# Sheet.net
KiCad netlist of a schematic drawn in Altium Designer
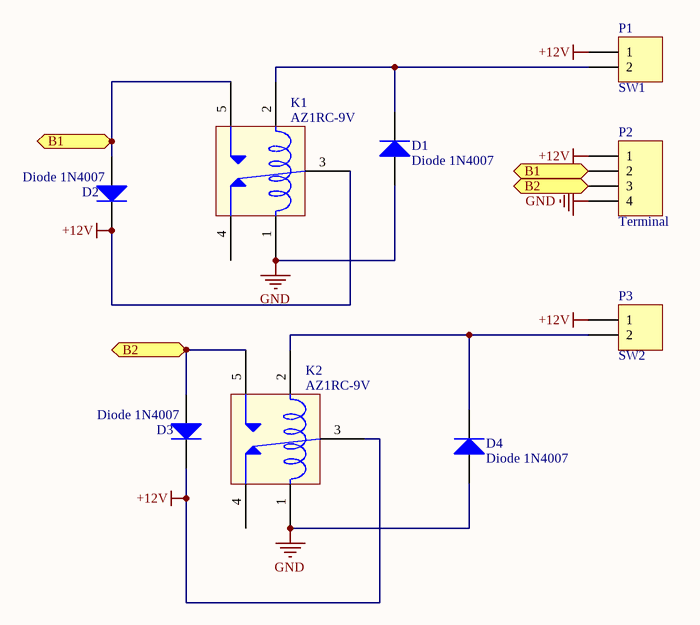
[diagram p0: Sheet.SchDoc]

(export (version "E")
  (design (tool "Eeschema 10.0.6"))
  (components
    (comp (ref "D1")
      (value "Diode 1N4007")
      (footprint "DO-41")
      (description "1 Amp General Purpose Rectifier")
      (fields (field (name "PUBLISHER") "Altium Limited"))
      (libsource (lib "Miscellaneous Devices (1)") (part "Diode 1N4007"))
    )
    (comp (ref "D2")
      (value "Diode 1N4007")
      (footprint "DO-41")
      (description "1 Amp General Purpose Rectifier")
      (fields (field (name "PUBLISHER") "Altium Limited"))
      (libsource (lib "Miscellaneous Devices (1)") (part "Diode 1N4007"))
    )
    (comp (ref "D3")
      (value "Diode 1N4007")
      (footprint "DO-41")
      (description "1 Amp General Purpose Rectifier")
      (fields (field (name "PUBLISHER") "Altium Limited"))
      (libsource (lib "Miscellaneous Devices (1)") (part "Diode 1N4007"))
    )
    (comp (ref "D4")
      (value "Diode 1N4007")
      (footprint "DO-41")
      (description "1 Amp General Purpose Rectifier")
      (fields (field (name "PUBLISHER") "Altium Limited"))
      (libsource (lib "Miscellaneous Devices (1)") (part "Diode 1N4007"))
    )
    (comp (ref "K1")
      (value "AZ1RC-9V")
      (footprint "Relay-A")
      (description "Miniature Relay, 10 A, 9 Vdc, 250 Vac")
      (libsource (lib "GPDSE") (part "AZ1RC-9V"))
    )
    (comp (ref "K2")
      (value "AZ1RC-9V")
      (footprint "Relay-A")
      (description "Miniature Relay, 10 A, 9 Vdc, 250 Vac")
      (libsource (lib "GPDSE") (part "AZ1RC-9V"))
    )
    (comp (ref "P1")
      (value "SW1")
      (footprint "KRE_2")
      (description "Terminal Block 1x2")
      (libsource (lib "GPDSE") (part "KRE_2"))
    )
    (comp (ref "P2")
      (value "Terminal")
      (footprint "KRE_4")
      (description "Terminal Block 1x4")
      (libsource (lib "GPDSE") (part "KRE_4"))
    )
    (comp (ref "P3")
      (value "SW2")
      (footprint "KRE_2")
      (description "Terminal Block 1x2")
      (libsource (lib "GPDSE") (part "KRE_2"))
    )
  )
  (nets
    (net (code "1") (name "+12V") (class "Default")
      (node (ref "D2") (pin "2") (pinfunction "K_2") (pintype "passive"))
      (node (ref "D3") (pin "2") (pinfunction "K_2") (pintype "passive"))
      (node (ref "K1") (pin "3") (pinfunction "3_3") (pintype "passive"))
      (node (ref "K2") (pin "3") (pinfunction "3_3") (pintype "passive"))
      (node (ref "P1") (pin "1") (pinfunction "1_1") (pintype "passive"))
      (node (ref "P2") (pin "1") (pinfunction "1_1") (pintype "passive"))
      (node (ref "P3") (pin "1") (pinfunction "1_1") (pintype "passive"))
    )
    (net (code "2") (name "/B1") (class "Default")
      (node (ref "D2") (pin "1") (pinfunction "A_1") (pintype "passive"))
      (node (ref "K1") (pin "5") (pinfunction "5_5") (pintype "passive"))
      (node (ref "P2") (pin "2") (pinfunction "2_2") (pintype "passive"))
    )
    (net (code "3") (name "/B2") (class "Default")
      (node (ref "D3") (pin "1") (pinfunction "A_1") (pintype "passive"))
      (node (ref "K2") (pin "5") (pinfunction "5_5") (pintype "passive"))
      (node (ref "P2") (pin "3") (pinfunction "3_3") (pintype "passive"))
    )
    (net (code "4") (name "GND") (class "Default")
      (node (ref "D1") (pin "1") (pinfunction "A_1") (pintype "passive"))
      (node (ref "D4") (pin "1") (pinfunction "A_1") (pintype "passive"))
      (node (ref "K1") (pin "1") (pinfunction "1_1") (pintype "passive"))
      (node (ref "K2") (pin "1") (pinfunction "1_1") (pintype "passive"))
      (node (ref "P2") (pin "4") (pinfunction "4_4") (pintype "passive"))
    )
    (net (code "5") (name "Net-(D1-K)") (class "Default")
      (node (ref "D1") (pin "2") (pinfunction "K_2") (pintype "passive"))
      (node (ref "K1") (pin "2") (pinfunction "2_2") (pintype "passive"))
      (node (ref "P1") (pin "2") (pinfunction "2_2") (pintype "passive"))
    )
    (net (code "6") (name "Net-(D4-K)") (class "Default")
      (node (ref "D4") (pin "2") (pinfunction "K_2") (pintype "passive"))
      (node (ref "K2") (pin "2") (pinfunction "2_2") (pintype "passive"))
      (node (ref "P3") (pin "2") (pinfunction "2_2") (pintype "passive"))
    )
    (net (code "7") (name "unconnected-(K1-Pad4)") (class "Default")
      (node (ref "K1") (pin "4") (pinfunction "4_4") (pintype "passive"))
    )
    (net (code "8") (name "unconnected-(K2-Pad4)") (class "Default")
      (node (ref "K2") (pin "4") (pinfunction "4_4") (pintype "passive"))
    )
  )
)
